# lda.net
KiCad netlist of a schematic drawn in EAGLE
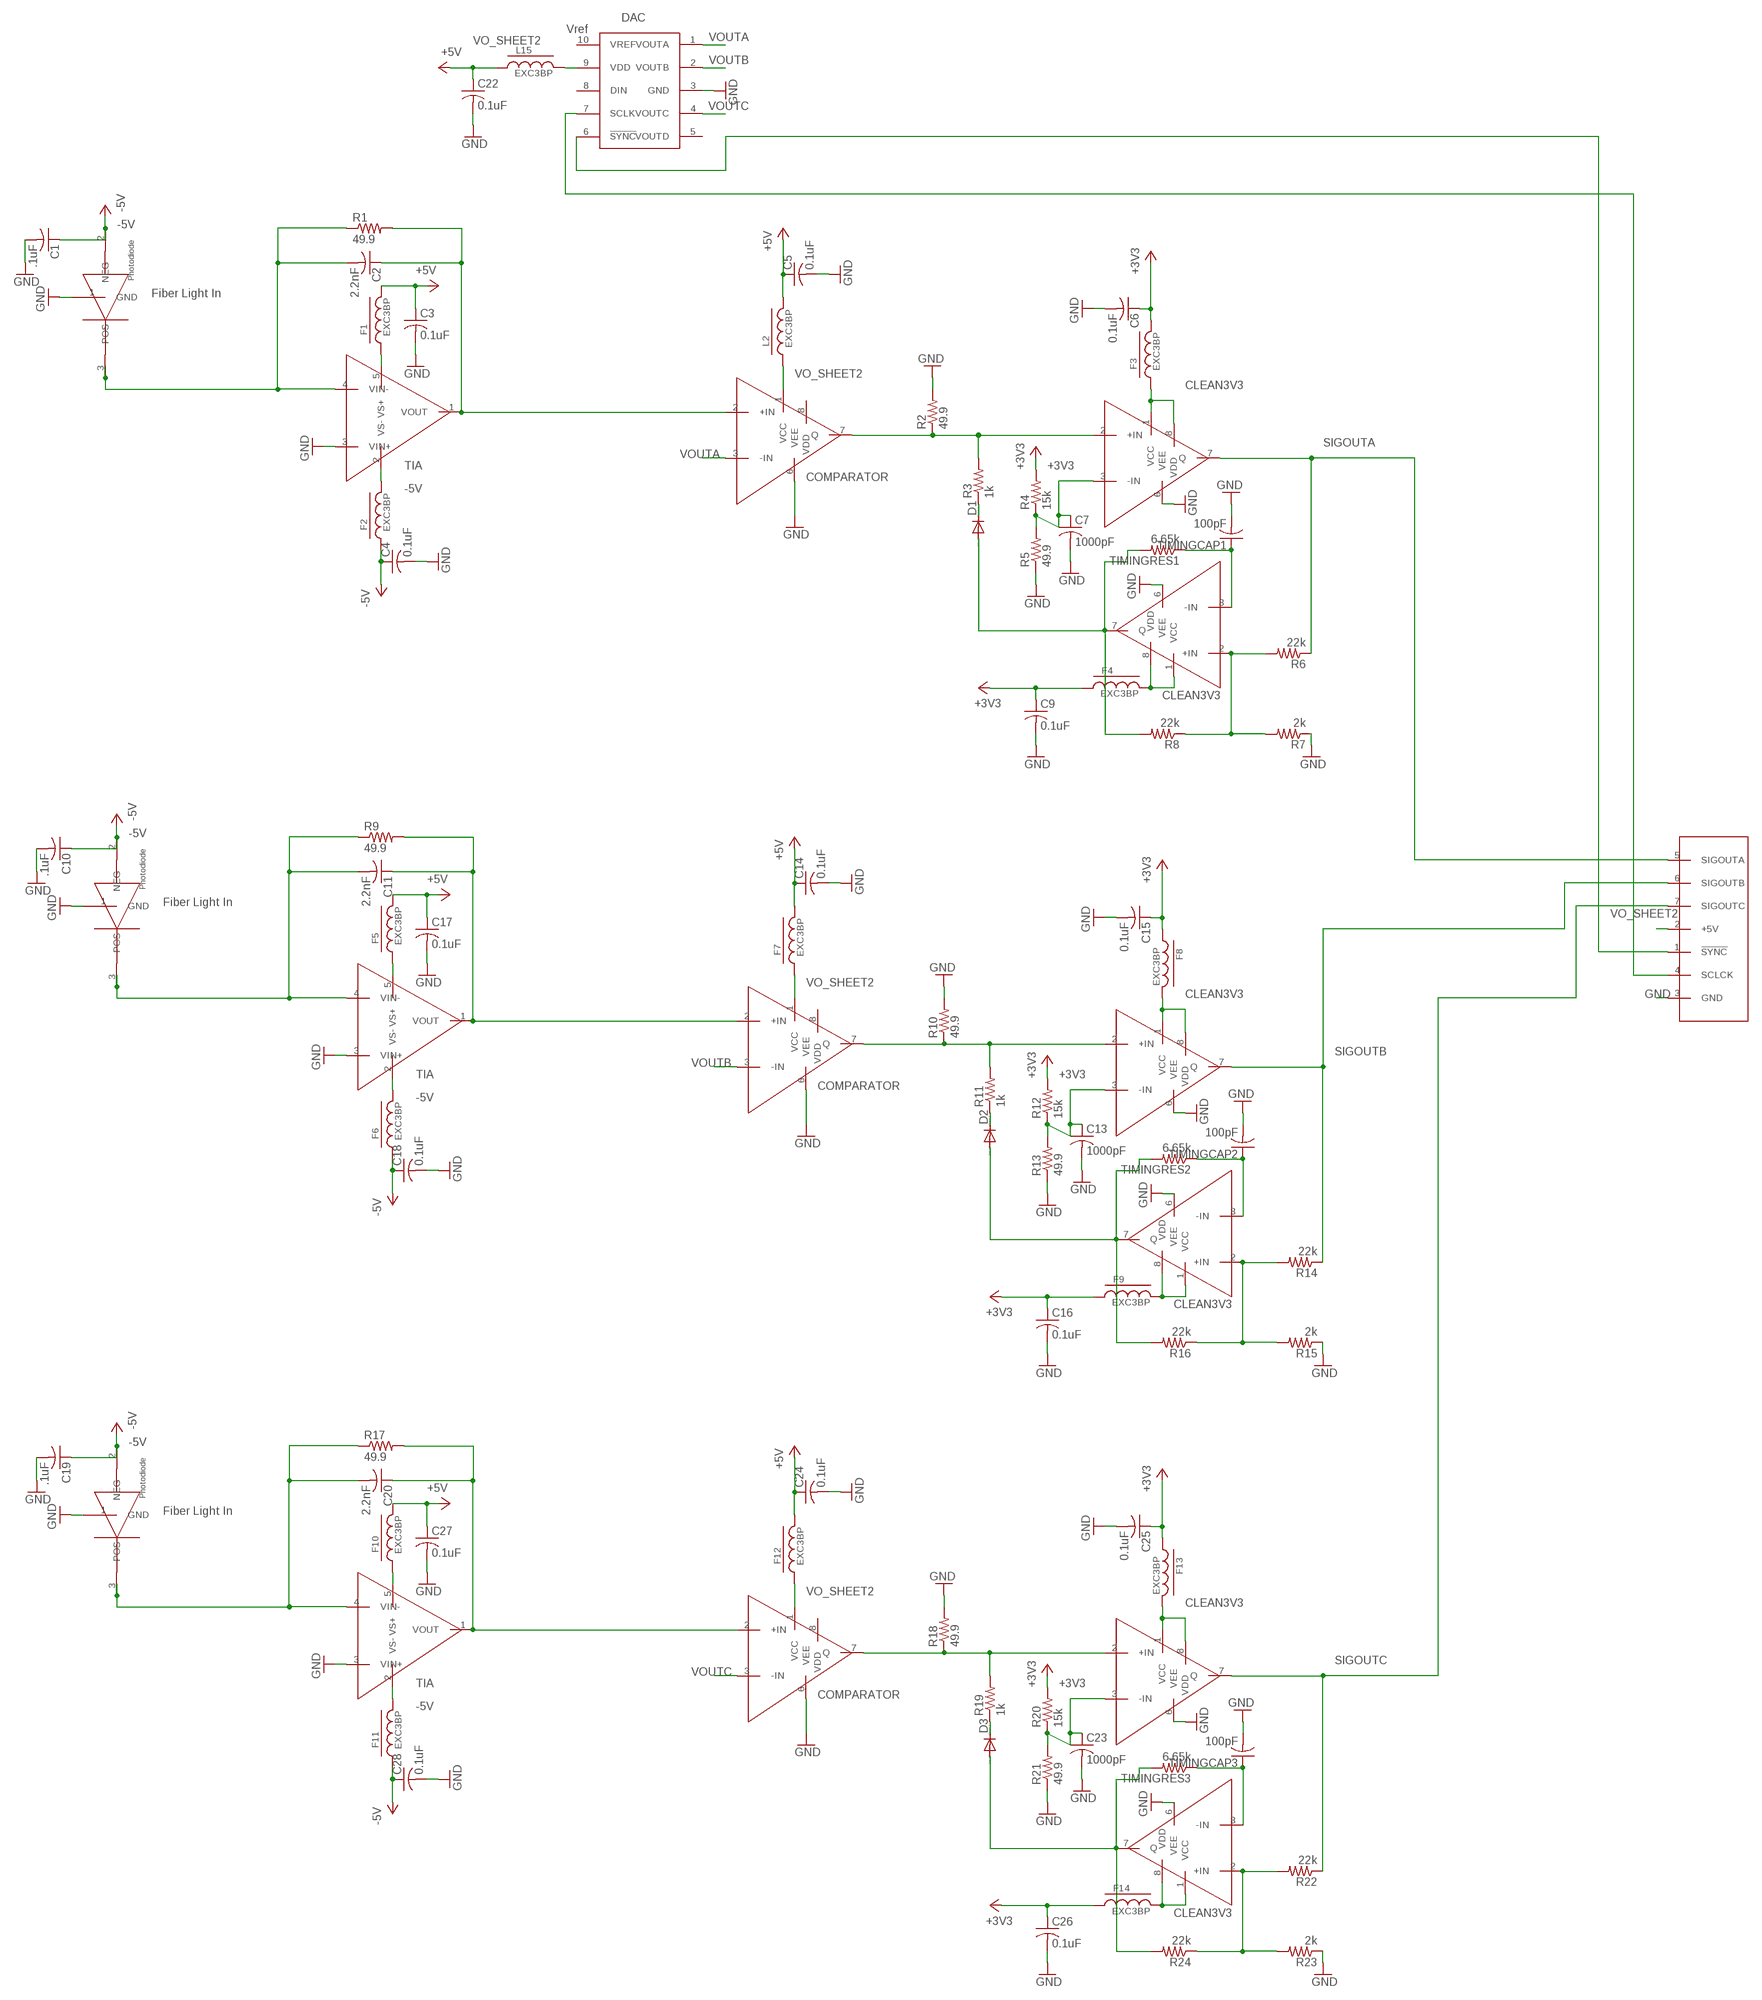
[diagram p0: schematic, sheet 1]
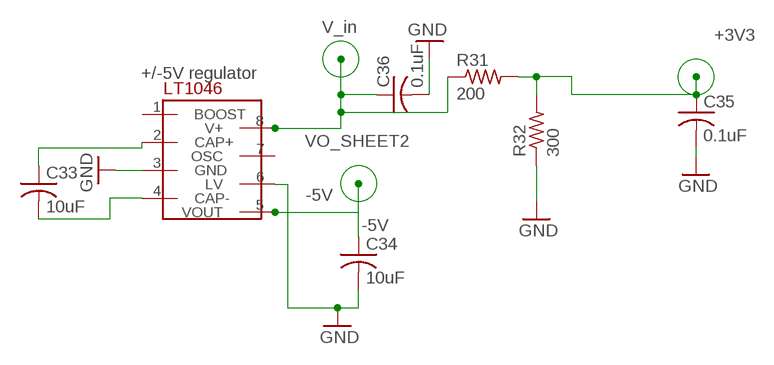
[diagram p1: schematic, sheet 2]

(export (version "E")
  (design (tool "Eeschema 10.0.6"))
  (components
    (comp (ref "C33")
      (value "10uF")
      (footprint "eagle-import:C01005")
      (libsource (lib "eagle-import") (part "C-US01005"))
    )
    (comp (ref "C34")
      (value "10uF")
      (footprint "eagle-import:C01005")
      (libsource (lib "eagle-import") (part "C-US01005"))
    )
    (comp (ref "C35")
      (value "0.1uF")
      (footprint "eagle-import:C01005")
      (libsource (lib "eagle-import") (part "C-US01005"))
    )
    (comp (ref "C36")
      (value "0.1uF")
      (footprint "eagle-import:C01005")
      (libsource (lib "eagle-import") (part "C-US01005"))
    )
    (comp (ref "R31")
      (value "200")
      (footprint "eagle-import:R01005")
      (libsource (lib "eagle-import") (part "R-US_01005"))
    )
    (comp (ref "R32")
      (value "300")
      (footprint "eagle-import:R01005")
      (libsource (lib "eagle-import") (part "R-US_01005"))
    )
    (comp (ref "U$1")
      (value "LT1046REG")
      (footprint "eagle-import:S8")
      (libsource (lib "eagle-import") (part "LT1046REG"))
    )
    (comp (ref "C1")
      (value ".1uF")
      (footprint "eagle-import:C01005")
      (libsource (lib "eagle-import") (part "C-US01005"))
    )
    (comp (ref "C2")
      (value "2.2nF")
      (footprint "eagle-import:C01005")
      (libsource (lib "eagle-import") (part "C-US01005"))
    )
    (comp (ref "C3")
      (value "0.1uF")
      (footprint "eagle-import:C01005")
      (libsource (lib "eagle-import") (part "C-US01005"))
    )
    (comp (ref "C4")
      (value "0.1uF")
      (footprint "eagle-import:C01005")
      (libsource (lib "eagle-import") (part "C-US01005"))
    )
    (comp (ref "C5")
      (value "0.1uF")
      (footprint "eagle-import:C01005")
      (libsource (lib "eagle-import") (part "C-US01005"))
    )
    (comp (ref "C6")
      (value "0.1uF")
      (footprint "eagle-import:C01005")
      (libsource (lib "eagle-import") (part "C-US01005"))
    )
    (comp (ref "C7")
      (value "1000pF")
      (footprint "eagle-import:C01005")
      (libsource (lib "eagle-import") (part "C-US01005"))
    )
    (comp (ref "C9")
      (value "0.1uF")
      (footprint "eagle-import:C01005")
      (libsource (lib "eagle-import") (part "C-US01005"))
    )
    (comp (ref "C10")
      (value ".1uF")
      (footprint "eagle-import:C01005")
      (libsource (lib "eagle-import") (part "C-US01005"))
    )
    (comp (ref "C11")
      (value "2.2nF")
      (footprint "eagle-import:C01005")
      (libsource (lib "eagle-import") (part "C-US01005"))
    )
    (comp (ref "C13")
      (value "1000pF")
      (footprint "eagle-import:C01005")
      (libsource (lib "eagle-import") (part "C-US01005"))
    )
    (comp (ref "C14")
      (value "0.1uF")
      (footprint "eagle-import:C01005")
      (libsource (lib "eagle-import") (part "C-US01005"))
    )
    (comp (ref "C15")
      (value "0.1uF")
      (footprint "eagle-import:C01005")
      (libsource (lib "eagle-import") (part "C-US01005"))
    )
    (comp (ref "C16")
      (value "0.1uF")
      (footprint "eagle-import:C01005")
      (libsource (lib "eagle-import") (part "C-US01005"))
    )
    (comp (ref "C17")
      (value "0.1uF")
      (footprint "eagle-import:C01005")
      (libsource (lib "eagle-import") (part "C-US01005"))
    )
    (comp (ref "C18")
      (value "0.1uF")
      (footprint "eagle-import:C01005")
      (libsource (lib "eagle-import") (part "C-US01005"))
    )
    (comp (ref "C19")
      (value ".1uF")
      (footprint "eagle-import:C01005")
      (libsource (lib "eagle-import") (part "C-US01005"))
    )
    (comp (ref "C20")
      (value "2.2nF")
      (footprint "eagle-import:C01005")
      (libsource (lib "eagle-import") (part "C-US01005"))
    )
    (comp (ref "C22")
      (value "0.1uF")
      (footprint "eagle-import:C01005")
      (libsource (lib "eagle-import") (part "C-US01005"))
    )
    (comp (ref "C23")
      (value "1000pF")
      (footprint "eagle-import:C01005")
      (libsource (lib "eagle-import") (part "C-US01005"))
    )
    (comp (ref "C24")
      (value "0.1uF")
      (footprint "eagle-import:C01005")
      (libsource (lib "eagle-import") (part "C-US01005"))
    )
    (comp (ref "C25")
      (value "0.1uF")
      (footprint "eagle-import:C01005")
      (libsource (lib "eagle-import") (part "C-US01005"))
    )
    (comp (ref "C26")
      (value "0.1uF")
      (footprint "eagle-import:C01005")
      (libsource (lib "eagle-import") (part "C-US01005"))
    )
    (comp (ref "C27")
      (value "0.1uF")
      (footprint "eagle-import:C01005")
      (libsource (lib "eagle-import") (part "C-US01005"))
    )
    (comp (ref "C28")
      (value "0.1uF")
      (footprint "eagle-import:C01005")
      (libsource (lib "eagle-import") (part "C-US01005"))
    )
    (comp (ref "COMPARATOR1")
      (value "LTC6752DEV")
      (footprint "eagle-import:MS8-MSOP")
      (libsource (lib "eagle-import") (part "LTC6752DEV"))
    )
    (comp (ref "COMPARATOR2")
      (value "LTC6752DEV")
      (footprint "eagle-import:MS8-MSOP")
      (libsource (lib "eagle-import") (part "LTC6752DEV"))
    )
    (comp (ref "COMPARATOR3")
      (value "LTC6752DEV")
      (footprint "eagle-import:MS8-MSOP")
      (libsource (lib "eagle-import") (part "LTC6752DEV"))
    )
    (comp (ref "COMPARATOR4")
      (value "LTC6752DEV")
      (footprint "eagle-import:MS8-MSOP")
      (libsource (lib "eagle-import") (part "LTC6752DEV"))
    )
    (comp (ref "COMPARATOR5")
      (value "LTC6752DEV")
      (footprint "eagle-import:MS8-MSOP")
      (libsource (lib "eagle-import") (part "LTC6752DEV"))
    )
    (comp (ref "COMPARATOR6")
      (value "LTC6752DEV")
      (footprint "eagle-import:MS8-MSOP")
      (libsource (lib "eagle-import") (part "LTC6752DEV"))
    )
    (comp (ref "COMPARATOR7")
      (value "LTC6752DEV")
      (footprint "eagle-import:MS8-MSOP")
      (libsource (lib "eagle-import") (part "LTC6752DEV"))
    )
    (comp (ref "COMPARATOR8")
      (value "LTC6752DEV")
      (footprint "eagle-import:MS8-MSOP")
      (libsource (lib "eagle-import") (part "LTC6752DEV"))
    )
    (comp (ref "COMPARATOR9")
      (value "LTC6752DEV")
      (footprint "eagle-import:MS8-MSOP")
      (libsource (lib "eagle-import") (part "LTC6752DEV"))
    )
    (comp (ref "D1")
      (value "DIODE-SOD523")
      (footprint "eagle-import:SOD523")
      (libsource (lib "eagle-import") (part "DIODE-SOD523"))
    )
    (comp (ref "D2")
      (value "DIODE-SOD523")
      (footprint "eagle-import:SOD523")
      (libsource (lib "eagle-import") (part "DIODE-SOD523"))
    )
    (comp (ref "D3")
      (value "DIODE-SOD523")
      (footprint "eagle-import:SOD523")
      (libsource (lib "eagle-import") (part "DIODE-SOD523"))
    )
    (comp (ref "DAC")
      (value "AD5624DEV")
      (footprint "eagle-import:AD5624MSOP")
      (libsource (lib "eagle-import") (part "AD5624DEV"))
    )
    (comp (ref "F1")
      (value "EXC3BP")
      (footprint "eagle-import:R01005")
      (libsource (lib "eagle-import") (part "EXC3BP"))
    )
    (comp (ref "F2")
      (value "EXC3BP")
      (footprint "eagle-import:R01005")
      (libsource (lib "eagle-import") (part "EXC3BP"))
    )
    (comp (ref "F3")
      (value "EXC3BP")
      (footprint "eagle-import:R01005")
      (libsource (lib "eagle-import") (part "EXC3BP"))
    )
    (comp (ref "F4")
      (value "EXC3BP")
      (footprint "eagle-import:R01005")
      (libsource (lib "eagle-import") (part "EXC3BP"))
    )
    (comp (ref "F5")
      (value "EXC3BP")
      (footprint "eagle-import:R01005")
      (libsource (lib "eagle-import") (part "EXC3BP"))
    )
    (comp (ref "F6")
      (value "EXC3BP")
      (footprint "eagle-import:R01005")
      (libsource (lib "eagle-import") (part "EXC3BP"))
    )
    (comp (ref "F7")
      (value "EXC3BP")
      (footprint "eagle-import:R01005")
      (libsource (lib "eagle-import") (part "EXC3BP"))
    )
    (comp (ref "F8")
      (value "EXC3BP")
      (footprint "eagle-import:R01005")
      (libsource (lib "eagle-import") (part "EXC3BP"))
    )
    (comp (ref "F9")
      (value "EXC3BP")
      (footprint "eagle-import:R01005")
      (libsource (lib "eagle-import") (part "EXC3BP"))
    )
    (comp (ref "F10")
      (value "EXC3BP")
      (footprint "eagle-import:R01005")
      (libsource (lib "eagle-import") (part "EXC3BP"))
    )
    (comp (ref "F11")
      (value "EXC3BP")
      (footprint "eagle-import:R01005")
      (libsource (lib "eagle-import") (part "EXC3BP"))
    )
    (comp (ref "F12")
      (value "EXC3BP")
      (footprint "eagle-import:R01005")
      (libsource (lib "eagle-import") (part "EXC3BP"))
    )
    (comp (ref "F13")
      (value "EXC3BP")
      (footprint "eagle-import:R01005")
      (libsource (lib "eagle-import") (part "EXC3BP"))
    )
    (comp (ref "F14")
      (value "EXC3BP")
      (footprint "eagle-import:R01005")
      (libsource (lib "eagle-import") (part "EXC3BP"))
    )
    (comp (ref "L2")
      (value "EXC3BP")
      (footprint "eagle-import:R01005")
      (libsource (lib "eagle-import") (part "EXC3BP"))
    )
    (comp (ref "L15")
      (value "EXC3BP")
      (footprint "eagle-import:R01005")
      (libsource (lib "eagle-import") (part "EXC3BP"))
    )
    (comp (ref "PD1")
      (value "EPM605DEV")
      (footprint "eagle-import:PINPDBOX")
      (libsource (lib "eagle-import") (part "EPM605DEV"))
    )
    (comp (ref "PD2")
      (value "EPM605DEV")
      (footprint "eagle-import:PINPDBOX")
      (libsource (lib "eagle-import") (part "EPM605DEV"))
    )
    (comp (ref "PD3")
      (value "EPM605DEV")
      (footprint "eagle-import:PINPDBOX")
      (libsource (lib "eagle-import") (part "EPM605DEV"))
    )
    (comp (ref "R1")
      (value "49.9")
      (footprint "eagle-import:R01005")
      (libsource (lib "eagle-import") (part "R-US_01005"))
    )
    (comp (ref "R2")
      (value "49.9")
      (footprint "eagle-import:R01005")
      (libsource (lib "eagle-import") (part "R-US_01005"))
    )
    (comp (ref "R3")
      (value "1k")
      (footprint "eagle-import:R01005")
      (libsource (lib "eagle-import") (part "R-US_01005"))
    )
    (comp (ref "R4")
      (value "15k")
      (footprint "eagle-import:R01005")
      (libsource (lib "eagle-import") (part "R-US_01005"))
    )
    (comp (ref "R5")
      (value "49.9")
      (footprint "eagle-import:R01005")
      (libsource (lib "eagle-import") (part "R-US_01005"))
    )
    (comp (ref "R6")
      (value "22k")
      (footprint "eagle-import:R01005")
      (libsource (lib "eagle-import") (part "R-US_01005"))
    )
    (comp (ref "R7")
      (value "2k")
      (footprint "eagle-import:R01005")
      (libsource (lib "eagle-import") (part "R-US_01005"))
    )
    (comp (ref "R8")
      (value "22k")
      (footprint "eagle-import:R01005")
      (libsource (lib "eagle-import") (part "R-US_01005"))
    )
    (comp (ref "R9")
      (value "49.9")
      (footprint "eagle-import:R01005")
      (libsource (lib "eagle-import") (part "R-US_01005"))
    )
    (comp (ref "R10")
      (value "49.9")
      (footprint "eagle-import:R01005")
      (libsource (lib "eagle-import") (part "R-US_01005"))
    )
    (comp (ref "R11")
      (value "1k")
      (footprint "eagle-import:R01005")
      (libsource (lib "eagle-import") (part "R-US_01005"))
    )
    (comp (ref "R12")
      (value "15k")
      (footprint "eagle-import:R01005")
      (libsource (lib "eagle-import") (part "R-US_01005"))
    )
    (comp (ref "R13")
      (value "49.9")
      (footprint "eagle-import:R01005")
      (libsource (lib "eagle-import") (part "R-US_01005"))
    )
    (comp (ref "R14")
      (value "22k")
      (footprint "eagle-import:R01005")
      (libsource (lib "eagle-import") (part "R-US_01005"))
    )
    (comp (ref "R15")
      (value "2k")
      (footprint "eagle-import:R01005")
      (libsource (lib "eagle-import") (part "R-US_01005"))
    )
    (comp (ref "R16")
      (value "22k")
      (footprint "eagle-import:R01005")
      (libsource (lib "eagle-import") (part "R-US_01005"))
    )
    (comp (ref "R17")
      (value "49.9")
      (footprint "eagle-import:R01005")
      (libsource (lib "eagle-import") (part "R-US_01005"))
    )
    (comp (ref "R18")
      (value "49.9")
      (footprint "eagle-import:R01005")
      (libsource (lib "eagle-import") (part "R-US_01005"))
    )
    (comp (ref "R19")
      (value "1k")
      (footprint "eagle-import:R01005")
      (libsource (lib "eagle-import") (part "R-US_01005"))
    )
    (comp (ref "R20")
      (value "15k")
      (footprint "eagle-import:R01005")
      (libsource (lib "eagle-import") (part "R-US_01005"))
    )
    (comp (ref "R21")
      (value "49.9")
      (footprint "eagle-import:R01005")
      (libsource (lib "eagle-import") (part "R-US_01005"))
    )
    (comp (ref "R22")
      (value "22k")
      (footprint "eagle-import:R01005")
      (libsource (lib "eagle-import") (part "R-US_01005"))
    )
    (comp (ref "R23")
      (value "2k")
      (footprint "eagle-import:R01005")
      (libsource (lib "eagle-import") (part "R-US_01005"))
    )
    (comp (ref "R24")
      (value "22k")
      (footprint "eagle-import:R01005")
      (libsource (lib "eagle-import") (part "R-US_01005"))
    )
    (comp (ref "TIA1")
      (value "OPA657DEV")
      (footprint "eagle-import:OPA-SOIC")
      (libsource (lib "eagle-import") (part "OPA657DEV"))
    )
    (comp (ref "TIA2")
      (value "OPA657DEV")
      (footprint "eagle-import:OPA-SOIC")
      (libsource (lib "eagle-import") (part "OPA657DEV"))
    )
    (comp (ref "TIA3")
      (value "OPA657DEV")
      (footprint "eagle-import:OPA-SOIC")
      (libsource (lib "eagle-import") (part "OPA657DEV"))
    )
    (comp (ref "TIMINGCAP1")
      (value "100pF")
      (footprint "eagle-import:C01005")
      (libsource (lib "eagle-import") (part "C-US01005"))
    )
    (comp (ref "TIMINGCAP2")
      (value "100pF")
      (footprint "eagle-import:C01005")
      (libsource (lib "eagle-import") (part "C-US01005"))
    )
    (comp (ref "TIMINGCAP3")
      (value "100pF")
      (footprint "eagle-import:C01005")
      (libsource (lib "eagle-import") (part "C-US01005"))
    )
    (comp (ref "TIMINGRES1")
      (value "6.65k")
      (footprint "eagle-import:R01005")
      (libsource (lib "eagle-import") (part "R-US_01005"))
    )
    (comp (ref "TIMINGRES2")
      (value "6.65k")
      (footprint "eagle-import:R01005")
      (libsource (lib "eagle-import") (part "R-US_01005"))
    )
    (comp (ref "TIMINGRES3")
      (value "6.65k")
      (footprint "eagle-import:R01005")
      (libsource (lib "eagle-import") (part "R-US_01005"))
    )
    (comp (ref "U$2")
      (value "SAMTEC7PIN")
      (footprint "eagle-import:SAMTEC7PIN")
      (libsource (lib "eagle-import") (part "SAMTEC7PIN"))
    )
  )
  (nets
    (net (code "1") (name "+3V3") (class "Default")
      (node (ref "C15") (pin "1") (pinfunction "1_1") (pintype "passive"))
      (node (ref "C16") (pin "1") (pinfunction "1_1") (pintype "passive"))
      (node (ref "C25") (pin "1") (pinfunction "1_1") (pintype "passive"))
      (node (ref "C26") (pin "1") (pinfunction "1_1") (pintype "passive"))
      (node (ref "C35") (pin "1") (pinfunction "1_1") (pintype "passive"))
      (node (ref "C6") (pin "1") (pinfunction "1_1") (pintype "passive"))
      (node (ref "C9") (pin "1") (pinfunction "1_1") (pintype "passive"))
      (node (ref "F13") (pin "1") (pinfunction "1_1") (pintype "passive"))
      (node (ref "F14") (pin "1") (pinfunction "1_1") (pintype "passive"))
      (node (ref "F3") (pin "2") (pinfunction "2_2") (pintype "passive"))
      (node (ref "F4") (pin "1") (pinfunction "1_1") (pintype "passive"))
      (node (ref "F8") (pin "1") (pinfunction "1_1") (pintype "passive"))
      (node (ref "F9") (pin "1") (pinfunction "1_1") (pintype "passive"))
      (node (ref "R12") (pin "2") (pinfunction "2_2") (pintype "passive"))
      (node (ref "R20") (pin "2") (pinfunction "2_2") (pintype "passive"))
      (node (ref "R31") (pin "2") (pinfunction "2_2") (pintype "passive"))
      (node (ref "R32") (pin "2") (pinfunction "2_2") (pintype "passive"))
      (node (ref "R4") (pin "2") (pinfunction "2_2") (pintype "passive"))
    )
    (net (code "2") (name "-5V") (class "Default")
      (node (ref "C1") (pin "1") (pinfunction "1_1") (pintype "passive"))
      (node (ref "C10") (pin "1") (pinfunction "1_1") (pintype "passive"))
      (node (ref "C18") (pin "1") (pinfunction "1_1") (pintype "passive"))
      (node (ref "C19") (pin "1") (pinfunction "1_1") (pintype "passive"))
      (node (ref "C28") (pin "1") (pinfunction "1_1") (pintype "passive"))
      (node (ref "C34") (pin "1") (pinfunction "1_1") (pintype "passive"))
      (node (ref "C4") (pin "1") (pinfunction "1_1") (pintype "passive"))
      (node (ref "F11") (pin "1") (pinfunction "1_1") (pintype "passive"))
      (node (ref "F2") (pin "1") (pinfunction "1_1") (pintype "passive"))
      (node (ref "F6") (pin "1") (pinfunction "1_1") (pintype "passive"))
      (node (ref "PD1") (pin "2") (pinfunction "NEG_2") (pintype "bidirectional"))
      (node (ref "PD2") (pin "2") (pinfunction "NEG_2") (pintype "bidirectional"))
      (node (ref "PD3") (pin "2") (pinfunction "NEG_2") (pintype "bidirectional"))
      (node (ref "U$1") (pin "5") (pinfunction "VOUT_5") (pintype "bidirectional"))
    )
    (net (code "3") (name "CLEAN3V3") (class "Default")
      (node (ref "COMPARATOR2") (pin "1") (pinfunction "VCC_1") (pintype "bidirectional"))
      (node (ref "COMPARATOR2") (pin "8") (pinfunction "VDD_8") (pintype "bidirectional"))
      (node (ref "COMPARATOR3") (pin "1") (pinfunction "VCC_1") (pintype "bidirectional"))
      (node (ref "COMPARATOR3") (pin "8") (pinfunction "VDD_8") (pintype "bidirectional"))
      (node (ref "COMPARATOR5") (pin "1") (pinfunction "VCC_1") (pintype "bidirectional"))
      (node (ref "COMPARATOR5") (pin "8") (pinfunction "VDD_8") (pintype "bidirectional"))
      (node (ref "COMPARATOR6") (pin "1") (pinfunction "VCC_1") (pintype "bidirectional"))
      (node (ref "COMPARATOR6") (pin "8") (pinfunction "VDD_8") (pintype "bidirectional"))
      (node (ref "COMPARATOR8") (pin "1") (pinfunction "VCC_1") (pintype "bidirectional"))
      (node (ref "COMPARATOR8") (pin "8") (pinfunction "VDD_8") (pintype "bidirectional"))
      (node (ref "COMPARATOR9") (pin "1") (pinfunction "VCC_1") (pintype "bidirectional"))
      (node (ref "COMPARATOR9") (pin "8") (pinfunction "VDD_8") (pintype "bidirectional"))
      (node (ref "F13") (pin "2") (pinfunction "2_2") (pintype "passive"))
      (node (ref "F14") (pin "2") (pinfunction "2_2") (pintype "passive"))
      (node (ref "F3") (pin "1") (pinfunction "1_1") (pintype "passive"))
      (node (ref "F4") (pin "2") (pinfunction "2_2") (pintype "passive"))
      (node (ref "F8") (pin "2") (pinfunction "2_2") (pintype "passive"))
      (node (ref "F9") (pin "2") (pinfunction "2_2") (pintype "passive"))
    )
    (net (code "4") (name "GND") (class "Default")
      (node (ref "C1") (pin "2") (pinfunction "2_2") (pintype "passive"))
      (node (ref "C10") (pin "2") (pinfunction "2_2") (pintype "passive"))
      (node (ref "C13") (pin "2") (pinfunction "2_2") (pintype "passive"))
      (node (ref "C14") (pin "2") (pinfunction "2_2") (pintype "passive"))
      (node (ref "C15") (pin "2") (pinfunction "2_2") (pintype "passive"))
      (node (ref "C16") (pin "2") (pinfunction "2_2") (pintype "passive"))
      (node (ref "C17") (pin "2") (pinfunction "2_2") (pintype "passive"))
      (node (ref "C18") (pin "2") (pinfunction "2_2") (pintype "passive"))
      (node (ref "C19") (pin "2") (pinfunction "2_2") (pintype "passive"))
      (node (ref "C22") (pin "2") (pinfunction "2_2") (pintype "passive"))
      (node (ref "C23") (pin "2") (pinfunction "2_2") (pintype "passive"))
      (node (ref "C24") (pin "2") (pinfunction "2_2") (pintype "passive"))
      (node (ref "C25") (pin "2") (pinfunction "2_2") (pintype "passive"))
      (node (ref "C26") (pin "2") (pinfunction "2_2") (pintype "passive"))
      (node (ref "C27") (pin "2") (pinfunction "2_2") (pintype "passive"))
      (node (ref "C28") (pin "2") (pinfunction "2_2") (pintype "passive"))
      (node (ref "C3") (pin "2") (pinfunction "2_2") (pintype "passive"))
      (node (ref "C34") (pin "2") (pinfunction "2_2") (pintype "passive"))
      (node (ref "C35") (pin "2") (pinfunction "2_2") (pintype "passive"))
      (node (ref "C36") (pin "2") (pinfunction "2_2") (pintype "passive"))
      (node (ref "C4") (pin "2") (pinfunction "2_2") (pintype "passive"))
      (node (ref "C5") (pin "2") (pinfunction "2_2") (pintype "passive"))
      (node (ref "C6") (pin "2") (pinfunction "2_2") (pintype "passive"))
      (node (ref "C7") (pin "2") (pinfunction "2_2") (pintype "passive"))
      (node (ref "C9") (pin "2") (pinfunction "2_2") (pintype "passive"))
      (node (ref "COMPARATOR1") (pin "6") (pinfunction "VEE_6") (pintype "bidirectional"))
      (node (ref "COMPARATOR2") (pin "6") (pinfunction "VEE_6") (pintype "bidirectional"))
      (node (ref "COMPARATOR3") (pin "6") (pinfunction "VEE_6") (pintype "bidirectional"))
      (node (ref "COMPARATOR4") (pin "6") (pinfunction "VEE_6") (pintype "bidirectional"))
      (node (ref "COMPARATOR5") (pin "6") (pinfunction "VEE_6") (pintype "bidirectional"))
      (node (ref "COMPARATOR6") (pin "6") (pinfunction "VEE_6") (pintype "bidirectional"))
      (node (ref "COMPARATOR7") (pin "6") (pinfunction "VEE_6") (pintype "bidirectional"))
      (node (ref "COMPARATOR8") (pin "6") (pinfunction "VEE_6") (pintype "bidirectional"))
      (node (ref "COMPARATOR9") (pin "6") (pinfunction "VEE_6") (pintype "bidirectional"))
      (node (ref "DAC") (pin "3") (pinfunction "GND_3") (pintype "bidirectional"))
      (node (ref "PD1") (pin "1") (pinfunction "GND_1") (pintype "bidirectional"))
      (node (ref "PD2") (pin "1") (pinfunction "GND_1") (pintype "bidirectional"))
      (node (ref "PD3") (pin "1") (pinfunction "GND_1") (pintype "bidirectional"))
      (node (ref "R10") (pin "2") (pinfunction "2_2") (pintype "passive"))
      (node (ref "R13") (pin "1") (pinfunction "1_1") (pintype "passive"))
      (node (ref "R15") (pin "1") (pinfunction "1_1") (pintype "passive"))
      (node (ref "R18") (pin "2") (pinfunction "2_2") (pintype "passive"))
      (node (ref "R2") (pin "2") (pinfunction "2_2") (pintype "passive"))
      (node (ref "R21") (pin "1") (pinfunction "1_1") (pintype "passive"))
      (node (ref "R23") (pin "1") (pinfunction "1_1") (pintype "passive"))
      (node (ref "R32") (pin "1") (pinfunction "1_1") (pintype "passive"))
      (node (ref "R5") (pin "1") (pinfunction "1_1") (pintype "passive"))
      (node (ref "R7") (pin "1") (pinfunction "1_1") (pintype "passive"))
      (node (ref "TIA1") (pin "3") (pinfunction "VIN+_3") (pintype "bidirectional"))
      (node (ref "TIA2") (pin "3") (pinfunction "VIN+_3") (pintype "bidirectional"))
      (node (ref "TIA3") (pin "3") (pinfunction "VIN+_3") (pintype "bidirectional"))
      (node (ref "TIMINGCAP1") (pin "2") (pinfunction "2_2") (pintype "passive"))
      (node (ref "TIMINGCAP2") (pin "2") (pinfunction "2_2") (pintype "passive"))
      (node (ref "TIMINGCAP3") (pin "2") (pinfunction "2_2") (pintype "passive"))
      (node (ref "U$1") (pin "3") (pinfunction "GND_3") (pintype "bidirectional"))
      (node (ref "U$1") (pin "6") (pinfunction "LV_6") (pintype "bidirectional"))
      (node (ref "U$2") (pin "3") (pinfunction "GND_3") (pintype "bidirectional"))
    )
    (net (code "5") (name "Net-(COMPARATOR1-+IN)") (class "Default")
      (node (ref "C2") (pin "1") (pinfunction "1_1") (pintype "passive"))
      (node (ref "COMPARATOR1") (pin "2") (pinfunction "+IN_2") (pintype "bidirectional"))
      (node (ref "R1") (pin "2") (pinfunction "2_2") (pintype "passive"))
      (node (ref "TIA1") (pin "1") (pinfunction "VOUT_1") (pintype "bidirectional"))
    )
    (net (code "6") (name "Net-(COMPARATOR1-Q)") (class "Default")
      (node (ref "COMPARATOR1") (pin "7") (pinfunction "Q_7") (pintype "bidirectional"))
      (node (ref "COMPARATOR2") (pin "2") (pinfunction "+IN_2") (pintype "bidirectional"))
      (node (ref "R2") (pin "1") (pinfunction "1_1") (pintype "passive"))
      (node (ref "R3") (pin "2") (pinfunction "2_2") (pintype "passive"))
    )
    (net (code "7") (name "Net-(COMPARATOR1-VCC)") (class "Default")
      (node (ref "COMPARATOR1") (pin "1") (pinfunction "VCC_1") (pintype "bidirectional"))
      (node (ref "L2") (pin "1") (pinfunction "1_1") (pintype "passive"))
    )
    (net (code "8") (name "Net-(COMPARATOR2--IN)") (class "Default")
      (node (ref "C7") (pin "1") (pinfunction "1_1") (pintype "passive"))
      (node (ref "COMPARATOR2") (pin "3") (pinfunction "-IN_3") (pintype "bidirectional"))
      (node (ref "R4") (pin "1") (pinfunction "1_1") (pintype "passive"))
      (node (ref "R5") (pin "2") (pinfunction "2_2") (pintype "passive"))
    )
    (net (code "9") (name "Net-(COMPARATOR3-+IN)") (class "Default")
      (node (ref "COMPARATOR3") (pin "2") (pinfunction "+IN_2") (pintype "bidirectional"))
      (node (ref "R6") (pin "2") (pinfunction "2_2") (pintype "passive"))
      (node (ref "R7") (pin "2") (pinfunction "2_2") (pintype "passive"))
      (node (ref "R8") (pin "1") (pinfunction "1_1") (pintype "passive"))
    )
    (net (code "10") (name "Net-(COMPARATOR3--IN)") (class "Default")
      (node (ref "COMPARATOR3") (pin "3") (pinfunction "-IN_3") (pintype "bidirectional"))
      (node (ref "TIMINGCAP1") (pin "1") (pinfunction "1_1") (pintype "passive"))
      (node (ref "TIMINGRES1") (pin "1") (pinfunction "1_1") (pintype "passive"))
    )
    (net (code "11") (name "Net-(COMPARATOR3-Q)") (class "Default")
      (node (ref "COMPARATOR3") (pin "7") (pinfunction "Q_7") (pintype "bidirectional"))
      (node (ref "D1") (pin "A") (pinfunction "A_A") (pintype "passive"))
      (node (ref "R8") (pin "2") (pinfunction "2_2") (pintype "passive"))
      (node (ref "TIMINGRES1") (pin "2") (pinfunction "2_2") (pintype "passive"))
    )
    (net (code "12") (name "Net-(COMPARATOR4-+IN)") (class "Default")
      (node (ref "C11") (pin "1") (pinfunction "1_1") (pintype "passive"))
      (node (ref "COMPARATOR4") (pin "2") (pinfunction "+IN_2") (pintype "bidirectional"))
      (node (ref "R9") (pin "2") (pinfunction "2_2") (pintype "passive"))
      (node (ref "TIA2") (pin "1") (pinfunction "VOUT_1") (pintype "bidirectional"))
    )
    (net (code "13") (name "Net-(COMPARATOR4-Q)") (class "Default")
      (node (ref "COMPARATOR4") (pin "7") (pinfunction "Q_7") (pintype "bidirectional"))
      (node (ref "COMPARATOR6") (pin "2") (pinfunction "+IN_2") (pintype "bidirectional"))
      (node (ref "R10") (pin "1") (pinfunction "1_1") (pintype "passive"))
      (node (ref "R11") (pin "2") (pinfunction "2_2") (pintype "passive"))
    )
    (net (code "14") (name "Net-(COMPARATOR4-VCC)") (class "Default")
      (node (ref "COMPARATOR4") (pin "1") (pinfunction "VCC_1") (pintype "bidirectional"))
      (node (ref "F7") (pin "1") (pinfunction "1_1") (pintype "passive"))
    )
    (net (code "15") (name "Net-(COMPARATOR5-+IN)") (class "Default")
      (node (ref "COMPARATOR5") (pin "2") (pinfunction "+IN_2") (pintype "bidirectional"))
      (node (ref "R14") (pin "2") (pinfunction "2_2") (pintype "passive"))
      (node (ref "R15") (pin "2") (pinfunction "2_2") (pintype "passive"))
      (node (ref "R16") (pin "1") (pinfunction "1_1") (pintype "passive"))
    )
    (net (code "16") (name "Net-(COMPARATOR5--IN)") (class "Default")
      (node (ref "COMPARATOR5") (pin "3") (pinfunction "-IN_3") (pintype "bidirectional"))
      (node (ref "TIMINGCAP2") (pin "1") (pinfunction "1_1") (pintype "passive"))
      (node (ref "TIMINGRES2") (pin "1") (pinfunction "1_1") (pintype "passive"))
    )
    (net (code "17") (name "Net-(COMPARATOR5-Q)") (class "Default")
      (node (ref "COMPARATOR5") (pin "7") (pinfunction "Q_7") (pintype "bidirectional"))
      (node (ref "D2") (pin "A") (pinfunction "A_A") (pintype "passive"))
      (node (ref "R16") (pin "2") (pinfunction "2_2") (pintype "passive"))
      (node (ref "TIMINGRES2") (pin "2") (pinfunction "2_2") (pintype "passive"))
    )
    (net (code "18") (name "Net-(COMPARATOR6--IN)") (class "Default")
      (node (ref "C13") (pin "1") (pinfunction "1_1") (pintype "passive"))
      (node (ref "COMPARATOR6") (pin "3") (pinfunction "-IN_3") (pintype "bidirectional"))
      (node (ref "R12") (pin "1") (pinfunction "1_1") (pintype "passive"))
      (node (ref "R13") (pin "2") (pinfunction "2_2") (pintype "passive"))
    )
    (net (code "19") (name "Net-(COMPARATOR7-+IN)") (class "Default")
      (node (ref "C20") (pin "1") (pinfunction "1_1") (pintype "passive"))
      (node (ref "COMPARATOR7") (pin "2") (pinfunction "+IN_2") (pintype "bidirectional"))
      (node (ref "R17") (pin "2") (pinfunction "2_2") (pintype "passive"))
      (node (ref "TIA3") (pin "1") (pinfunction "VOUT_1") (pintype "bidirectional"))
    )
    (net (code "20") (name "Net-(COMPARATOR7-Q)") (class "Default")
      (node (ref "COMPARATOR7") (pin "7") (pinfunction "Q_7") (pintype "bidirectional"))
      (node (ref "COMPARATOR9") (pin "2") (pinfunction "+IN_2") (pintype "bidirectional"))
      (node (ref "R18") (pin "1") (pinfunction "1_1") (pintype "passive"))
      (node (ref "R19") (pin "2") (pinfunction "2_2") (pintype "passive"))
    )
    (net (code "21") (name "Net-(COMPARATOR7-VCC)") (class "Default")
      (node (ref "COMPARATOR7") (pin "1") (pinfunction "VCC_1") (pintype "bidirectional"))
      (node (ref "F12") (pin "1") (pinfunction "1_1") (pintype "passive"))
    )
    (net (code "22") (name "Net-(COMPARATOR8-+IN)") (class "Default")
      (node (ref "COMPARATOR8") (pin "2") (pinfunction "+IN_2") (pintype "bidirectional"))
      (node (ref "R22") (pin "2") (pinfunction "2_2") (pintype "passive"))
      (node (ref "R23") (pin "2") (pinfunction "2_2") (pintype "passive"))
      (node (ref "R24") (pin "1") (pinfunction "1_1") (pintype "passive"))
    )
    (net (code "23") (name "Net-(COMPARATOR8--IN)") (class "Default")
      (node (ref "COMPARATOR8") (pin "3") (pinfunction "-IN_3") (pintype "bidirectional"))
      (node (ref "TIMINGCAP3") (pin "1") (pinfunction "1_1") (pintype "passive"))
      (node (ref "TIMINGRES3") (pin "1") (pinfunction "1_1") (pintype "passive"))
    )
    (net (code "24") (name "Net-(COMPARATOR8-Q)") (class "Default")
      (node (ref "COMPARATOR8") (pin "7") (pinfunction "Q_7") (pintype "bidirectional"))
      (node (ref "D3") (pin "A") (pinfunction "A_A") (pintype "passive"))
      (node (ref "R24") (pin "2") (pinfunction "2_2") (pintype "passive"))
      (node (ref "TIMINGRES3") (pin "2") (pinfunction "2_2") (pintype "passive"))
    )
    (net (code "25") (name "Net-(COMPARATOR9--IN)") (class "Default")
      (node (ref "C23") (pin "1") (pinfunction "1_1") (pintype "passive"))
      (node (ref "COMPARATOR9") (pin "3") (pinfunction "-IN_3") (pintype "bidirectional"))
      (node (ref "R20") (pin "1") (pinfunction "1_1") (pintype "passive"))
      (node (ref "R21") (pin "2") (pinfunction "2_2") (pintype "passive"))
    )
    (net (code "26") (name "Net-(D1-PadC)") (class "Default")
      (node (ref "D1") (pin "C") (pinfunction "C_C") (pintype "passive"))
      (node (ref "R3") (pin "1") (pinfunction "1_1") (pintype "passive"))
    )
    (net (code "27") (name "Net-(D2-PadC)") (class "Default")
      (node (ref "D2") (pin "C") (pinfunction "C_C") (pintype "passive"))
      (node (ref "R11") (pin "1") (pinfunction "1_1") (pintype "passive"))
    )
    (net (code "28") (name "Net-(D3-PadC)") (class "Default")
      (node (ref "D3") (pin "C") (pinfunction "C_C") (pintype "passive"))
      (node (ref "R19") (pin "1") (pinfunction "1_1") (pintype "passive"))
    )
    (net (code "29") (name "Net-(DAC-SCLK)") (class "Default")
      (node (ref "DAC") (pin "7") (pinfunction "SCLK_7") (pintype "bidirectional"))
      (node (ref "U$2") (pin "4") (pinfunction "SCLCK_4") (pintype "bidirectional"))
    )
    (net (code "30") (name "Net-(DAC-VDD)") (class "Default")
      (node (ref "DAC") (pin "9") (pinfunction "VDD_9") (pintype "bidirectional"))
      (node (ref "L15") (pin "2") (pinfunction "2_2") (pintype "passive"))
    )
    (net (code "31") (name "Net-(DAC-~{SYNC})") (class "Default")
      (node (ref "DAC") (pin "6") (pinfunction "~{SYNC}_6") (pintype "bidirectional"))
      (node (ref "U$2") (pin "1") (pinfunction "~{SYNC}_1") (pintype "bidirectional"))
    )
    (net (code "32") (name "Net-(PD1-POS)") (class "Default")
      (node (ref "C2") (pin "2") (pinfunction "2_2") (pintype "passive"))
      (node (ref "PD1") (pin "3") (pinfunction "POS_3") (pintype "bidirectional"))
      (node (ref "R1") (pin "1") (pinfunction "1_1") (pintype "passive"))
      (node (ref "TIA1") (pin "4") (pinfunction "VIN-_4") (pintype "bidirectional"))
    )
    (net (code "33") (name "Net-(PD2-POS)") (class "Default")
      (node (ref "C11") (pin "2") (pinfunction "2_2") (pintype "passive"))
      (node (ref "PD2") (pin "3") (pinfunction "POS_3") (pintype "bidirectional"))
      (node (ref "R9") (pin "1") (pinfunction "1_1") (pintype "passive"))
      (node (ref "TIA2") (pin "4") (pinfunction "VIN-_4") (pintype "bidirectional"))
    )
    (net (code "34") (name "Net-(PD3-POS)") (class "Default")
      (node (ref "C20") (pin "2") (pinfunction "2_2") (pintype "passive"))
      (node (ref "PD3") (pin "3") (pinfunction "POS_3") (pintype "bidirectional"))
      (node (ref "R17") (pin "1") (pinfunction "1_1") (pintype "passive"))
      (node (ref "TIA3") (pin "4") (pinfunction "VIN-_4") (pintype "bidirectional"))
    )
    (net (code "35") (name "Net-(TIA1-VS+)") (class "Default")
      (node (ref "F1") (pin "1") (pinfunction "1_1") (pintype "passive"))
      (node (ref "TIA1") (pin "5") (pinfunction "VS+_5") (pintype "bidirectional"))
    )
    (net (code "36") (name "Net-(TIA1-VS-)") (class "Default")
      (node (ref "F2") (pin "2") (pinfunction "2_2") (pintype "passive"))
      (node (ref "TIA1") (pin "2") (pinfunction "VS-_2") (pintype "bidirectional"))
    )
    (net (code "37") (name "Net-(TIA2-VS+)") (class "Default")
      (node (ref "F5") (pin "1") (pinfunction "1_1") (pintype "passive"))
      (node (ref "TIA2") (pin "5") (pinfunction "VS+_5") (pintype "bidirectional"))
    )
    (net (code "38") (name "Net-(TIA2-VS-)") (class "Default")
      (node (ref "F6") (pin "2") (pinfunction "2_2") (pintype "passive"))
      (node (ref "TIA2") (pin "2") (pinfunction "VS-_2") (pintype "bidirectional"))
    )
    (net (code "39") (name "Net-(TIA3-VS+)") (class "Default")
      (node (ref "F10") (pin "1") (pinfunction "1_1") (pintype "passive"))
      (node (ref "TIA3") (pin "5") (pinfunction "VS+_5") (pintype "bidirectional"))
    )
    (net (code "40") (name "Net-(TIA3-VS-)") (class "Default")
      (node (ref "F11") (pin "2") (pinfunction "2_2") (pintype "passive"))
      (node (ref "TIA3") (pin "2") (pinfunction "VS-_2") (pintype "bidirectional"))
    )
    (net (code "41") (name "Net-(U$1-CAP+)") (class "Default")
      (node (ref "C33") (pin "1") (pinfunction "1_1") (pintype "passive"))
      (node (ref "U$1") (pin "2") (pinfunction "CAP+_2") (pintype "bidirectional"))
    )
    (net (code "42") (name "Net-(U$1-CAP-)") (class "Default")
      (node (ref "C33") (pin "2") (pinfunction "2_2") (pintype "passive"))
      (node (ref "U$1") (pin "4") (pinfunction "CAP-_4") (pintype "bidirectional"))
    )
    (net (code "43") (name "SIGOUTA") (class "Default")
      (node (ref "COMPARATOR2") (pin "7") (pinfunction "Q_7") (pintype "bidirectional"))
      (node (ref "R6") (pin "1") (pinfunction "1_1") (pintype "passive"))
      (node (ref "U$2") (pin "5") (pinfunction "SIGOUTA_5") (pintype "bidirectional"))
    )
    (net (code "44") (name "SIGOUTB") (class "Default")
      (node (ref "COMPARATOR6") (pin "7") (pinfunction "Q_7") (pintype "bidirectional"))
      (node (ref "R14") (pin "1") (pinfunction "1_1") (pintype "passive"))
      (node (ref "U$2") (pin "6") (pinfunction "SIGOUTB_6") (pintype "bidirectional"))
    )
    (net (code "45") (name "SIGOUTC") (class "Default")
      (node (ref "COMPARATOR9") (pin "7") (pinfunction "Q_7") (pintype "bidirectional"))
      (node (ref "R22") (pin "1") (pinfunction "1_1") (pintype "passive"))
      (node (ref "U$2") (pin "7") (pinfunction "SIGOUTC_7") (pintype "bidirectional"))
    )
    (net (code "46") (name "VOUTA") (class "Default")
      (node (ref "COMPARATOR1") (pin "3") (pinfunction "-IN_3") (pintype "bidirectional"))
      (node (ref "DAC") (pin "1") (pinfunction "VOUTA_1") (pintype "bidirectional"))
    )
    (net (code "47") (name "VOUTB") (class "Default")
      (node (ref "COMPARATOR4") (pin "3") (pinfunction "-IN_3") (pintype "bidirectional"))
      (node (ref "DAC") (pin "2") (pinfunction "VOUTB_2") (pintype "bidirectional"))
    )
    (net (code "48") (name "VOUTC") (class "Default")
      (node (ref "COMPARATOR7") (pin "3") (pinfunction "-IN_3") (pintype "bidirectional"))
      (node (ref "DAC") (pin "4") (pinfunction "VOUTC_4") (pintype "bidirectional"))
    )
    (net (code "49") (name "VO_SHEET2") (class "Default")
      (node (ref "C14") (pin "1") (pinfunction "1_1") (pintype "passive"))
      (node (ref "C17") (pin "1") (pinfunction "1_1") (pintype "passive"))
      (node (ref "C22") (pin "1") (pinfunction "1_1") (pintype "passive"))
      (node (ref "C24") (pin "1") (pinfunction "1_1") (pintype "passive"))
      (node (ref "C27") (pin "1") (pinfunction "1_1") (pintype "passive"))
      (node (ref "C3") (pin "1") (pinfunction "1_1") (pintype "passive"))
      (node (ref "C36") (pin "1") (pinfunction "1_1") (pintype "passive"))
      (node (ref "C5") (pin "1") (pinfunction "1_1") (pintype "passive"))
      (node (ref "F1") (pin "2") (pinfunction "2_2") (pintype "passive"))
      (node (ref "F10") (pin "2") (pinfunction "2_2") (pintype "passive"))
      (node (ref "F12") (pin "2") (pinfunction "2_2") (pintype "passive"))
      (node (ref "F5") (pin "2") (pinfunction "2_2") (pintype "passive"))
      (node (ref "F7") (pin "2") (pinfunction "2_2") (pintype "passive"))
      (node (ref "L15") (pin "1") (pinfunction "1_1") (pintype "passive"))
      (node (ref "L2") (pin "2") (pinfunction "2_2") (pintype "passive"))
      (node (ref "R31") (pin "1") (pinfunction "1_1") (pintype "passive"))
      (node (ref "U$1") (pin "8") (pinfunction "V+_8") (pintype "bidirectional"))
      (node (ref "U$2") (pin "2") (pinfunction "+5V_2") (pintype "bidirectional"))
    )
    (net (code "50") (name "unconnected-(COMPARATOR1-VDD-Pad8)") (class "Default")
      (node (ref "COMPARATOR1") (pin "8") (pinfunction "VDD_8") (pintype "bidirectional"))
    )
    (net (code "51") (name "unconnected-(COMPARATOR4-VDD-Pad8)") (class "Default")
      (node (ref "COMPARATOR4") (pin "8") (pinfunction "VDD_8") (pintype "bidirectional"))
    )
    (net (code "52") (name "unconnected-(COMPARATOR7-VDD-Pad8)") (class "Default")
      (node (ref "COMPARATOR7") (pin "8") (pinfunction "VDD_8") (pintype "bidirectional"))
    )
    (net (code "53") (name "unconnected-(DAC-DIN-Pad8)") (class "Default")
      (node (ref "DAC") (pin "8") (pinfunction "DIN_8") (pintype "bidirectional"))
    )
    (net (code "54") (name "unconnected-(DAC-VOUTD-Pad5)") (class "Default")
      (node (ref "DAC") (pin "5") (pinfunction "VOUTD_5") (pintype "bidirectional"))
    )
    (net (code "55") (name "unconnected-(DAC-VREF-Pad10)") (class "Default")
      (node (ref "DAC") (pin "10") (pinfunction "VREF_10") (pintype "bidirectional"))
    )
    (net (code "56") (name "unconnected-(U$1-BOOST-Pad1)") (class "Default")
      (node (ref "U$1") (pin "1") (pinfunction "BOOST_1") (pintype "bidirectional"))
    )
    (net (code "57") (name "unconnected-(U$1-OSC-Pad7)") (class "Default")
      (node (ref "U$1") (pin "7") (pinfunction "OSC_7") (pintype "bidirectional"))
    )
  )
)
